# preamp.net
KiCad netlist of a schematic drawn in Altium Designer
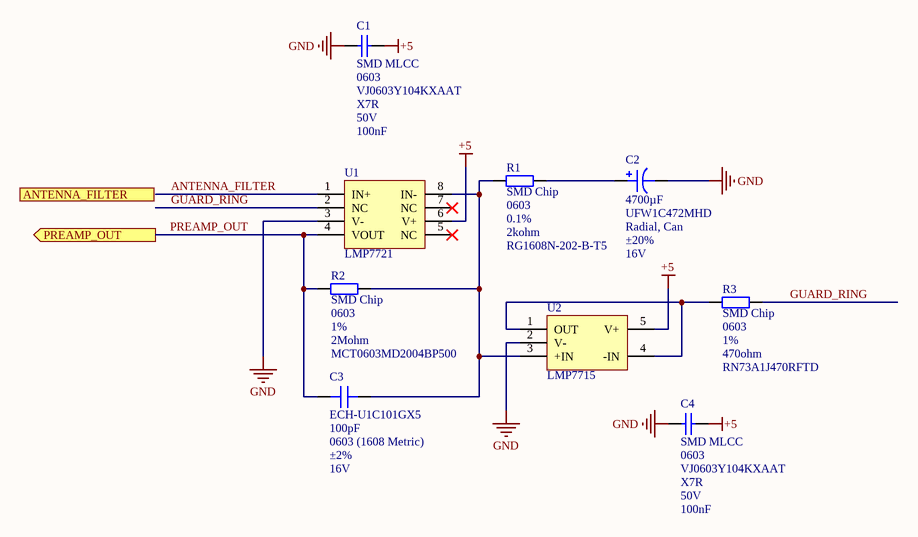
[diagram p0: preamp.SchDoc]

(export (version "E")
  (design (tool "Eeschema 10.0.6"))
  (components
    (comp (ref "C1")
      (value "SMD MLCC")
      (footprint "SMD_MLCC_CAPACITOR_0603")
      (description "generic SMD MLCC capacitor")
      (fields
        (field (name "SIZE") "0603")
        (field (name "PART NUMBER") "VJ0603Y104KXAAT")
        (field (name "DIELECTRIC") "X7R")
        (field (name "VOLTAGERATING") "50V")
        (field (name "CAPACITANCE") "100nF")
      )
      (libsource (lib "altium_library") (part "SMD MLCC Capacitor"))
    )
    (comp (ref "C2")
      (value "4700µF")
      (footprint "CAP TH ALUM ELEC D16.00mm S7.50mm H25.00mm")
      (description "CAP ALUM 4700UF 20% 16V RADIAL")
      (fields
        (field (name "PART NUMBER") "UFW1C472MHD")
        (field (name "MANUFACTURER") "Nichicon")
        (field (name "PACKAGE / CASE") "Radial, Can")
        (field (name "TOLERANCE") "±20%")
        (field (name "VOLTAGE - RATED") "16V")
      )
      (libsource (lib "Celestial Altium Library - altium_library") (part "Polarised Capacitor"))
    )
    (comp (ref "C3")
      (value "100pF")
      (footprint "CAP FILM 0603_1608")
      (description "CAP FILM 100PF 2% 16VDC 0603")
      (fields
        (field (name "PART NUMBER") "ECH-U1C101GX5")
        (field (name "CAPACITANCE") "100pF")
        (field (name "MANUFACTURER") "Panasonic Electronic Components")
        (field (name "PACKAGE / CASE") "0603 (1608 Metric)")
        (field (name "TOLERANCE") "±2%")
        (field (name "VOLTAGE RATING - DC") "16V")
      )
      (libsource (lib "Celestial Altium Library - altium_library") (part "Capacitor"))
    )
    (comp (ref "C4")
      (value "SMD MLCC")
      (footprint "SMD_MLCC_CAPACITOR_0603")
      (description "generic SMD MLCC capacitor")
      (fields
        (field (name "SIZE") "0603")
        (field (name "PART NUMBER") "VJ0603Y104KXAAT")
        (field (name "DIELECTRIC") "X7R")
        (field (name "VOLTAGERATING") "50V")
        (field (name "CAPACITANCE") "100nF")
      )
      (libsource (lib "altium_library") (part "SMD MLCC Capacitor"))
    )
    (comp (ref "R1")
      (value "SMD Chip")
      (footprint "SMD_CHIP_RESISTOR_0603")
      (description "generic SMD chip resistor")
      (fields
        (field (name "SIZE") "0603")
        (field (name "TOLERANCE") "0.1%")
        (field (name "RESISTANCE") "2kohm")
        (field (name "PART NUMBER") "RG1608N-202-B-T5")
      )
      (libsource (lib "altium_library") (part "SMD Chip Resistor"))
    )
    (comp (ref "R2")
      (value "SMD Chip")
      (footprint "SMD_CHIP_RESISTOR_0603")
      (description "generic SMD chip resistor")
      (fields
        (field (name "SIZE") "0603")
        (field (name "TOLERANCE") "1%")
        (field (name "RESISTANCE") "2Mohm")
        (field (name "PART NUMBER") "MCT0603MD2004BP500")
      )
      (libsource (lib "altium_library") (part "SMD Chip Resistor"))
    )
    (comp (ref "R3")
      (value "SMD Chip")
      (footprint "SMD_CHIP_RESISTOR_0603")
      (description "generic SMD chip resistor")
      (fields
        (field (name "SIZE") "0603")
        (field (name "TOLERANCE") "1%")
        (field (name "RESISTANCE") "470ohm")
        (field (name "PART NUMBER") "RN73A1J470RFTD")
      )
      (libsource (lib "altium_library") (part "SMD Chip Resistor"))
    )
    (comp (ref "U1")
      (value "LMP7721")
      (footprint "LMP7721")
      (description "3-femtoampere input bias current precision amplifier")
      (libsource (lib "altium_library") (part "LMP7721"))
    )
    (comp (ref "U2")
      (value "LMP7715")
      (footprint "LMP7715")
      (description "Precision, 17 MHz, Low Noise, CMOS Input Amplifier")
      (libsource (lib "altium_library") (part "LMP7715"))
    )
  )
  (nets
    (net (code "1") (name "+5") (class "Default")
      (node (ref "C1") (pin "1") (pinfunction "1_1") (pintype "passive"))
      (node (ref "C4") (pin "1") (pinfunction "1_1") (pintype "passive"))
      (node (ref "U1") (pin "6") (pinfunction "V+_6") (pintype "passive"))
      (node (ref "U2") (pin "5") (pinfunction "V+_5") (pintype "passive"))
    )
    (net (code "2") (name "/ANTENNA_FILTER") (class "Default")
      (node (ref "U1") (pin "1") (pinfunction "IN+_1") (pintype "passive"))
    )
    (net (code "3") (name "/GUARD_RING") (class "Default")
      (node (ref "R3") (pin "2") (pinfunction "2_2") (pintype "passive"))
      (node (ref "U1") (pin "2") (pinfunction "NC_2") (pintype "passive"))
    )
    (net (code "4") (name "/PREAMP_OUT") (class "Default")
      (node (ref "C3") (pin "1") (pinfunction "1_1") (pintype "passive"))
      (node (ref "R2") (pin "1") (pinfunction "1_1") (pintype "passive"))
      (node (ref "U1") (pin "4") (pinfunction "VOUT_4") (pintype "passive"))
    )
    (net (code "5") (name "GND") (class "Default")
      (node (ref "C1") (pin "2") (pinfunction "2_2") (pintype "passive"))
      (node (ref "C2") (pin "2") (pinfunction "2_2") (pintype "passive"))
      (node (ref "C4") (pin "2") (pinfunction "2_2") (pintype "passive"))
      (node (ref "U1") (pin "3") (pinfunction "V-_3") (pintype "passive"))
      (node (ref "U2") (pin "2") (pinfunction "V-_2") (pintype "passive"))
    )
    (net (code "6") (name "Net-(C2-Pad1)") (class "Default")
      (node (ref "C2") (pin "1") (pinfunction "1_1") (pintype "passive"))
      (node (ref "R1") (pin "2") (pinfunction "2_2") (pintype "passive"))
    )
    (net (code "7") (name "Net-(U1-IN-)") (class "Default")
      (node (ref "C3") (pin "2") (pinfunction "2_2") (pintype "passive"))
      (node (ref "R1") (pin "1") (pinfunction "1_1") (pintype "passive"))
      (node (ref "R2") (pin "2") (pinfunction "2_2") (pintype "passive"))
      (node (ref "U1") (pin "8") (pinfunction "IN-_8") (pintype "passive"))
      (node (ref "U2") (pin "3") (pinfunction "+IN_3") (pintype "passive"))
    )
    (net (code "8") (name "Net-(U2--IN)") (class "Default")
      (node (ref "R3") (pin "1") (pinfunction "1_1") (pintype "passive"))
      (node (ref "U2") (pin "1") (pinfunction "OUT_1") (pintype "passive"))
      (node (ref "U2") (pin "4") (pinfunction "-IN_4") (pintype "passive"))
    )
    (net (code "9") (name "unconnected-(U1-NC-Pad5)") (class "Default")
      (node (ref "U1") (pin "5") (pinfunction "NC_5") (pintype "passive+no_connect"))
    )
    (net (code "10") (name "unconnected-(U1-NC-Pad7)") (class "Default")
      (node (ref "U1") (pin "7") (pinfunction "NC_7") (pintype "passive+no_connect"))
    )
  )
)
